# SRAM.net
KiCad netlist of a schematic drawn in Altium Designer
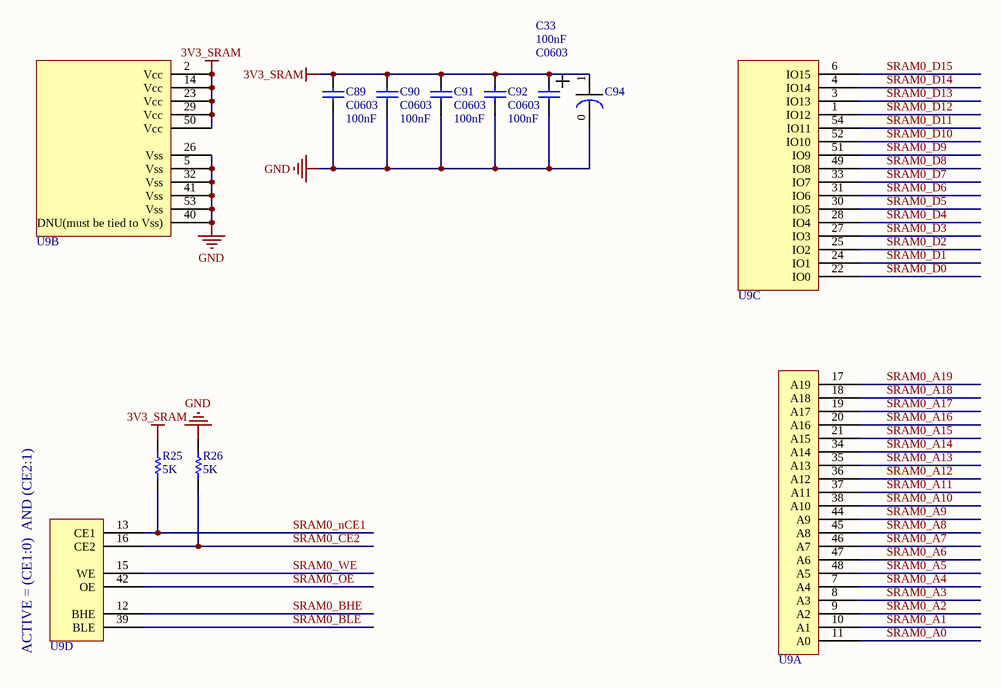
[diagram p0: SRAM.SchDoc]

(export (version "E")
  (design (tool "Eeschema 10.0.6"))
  (components
    (comp (ref "C33")
      (value "C0603")
      (footprint "0603")
      (description "Ceramic Chip Capacitor - Standard")
      (fields (field (name "ALTIUM_VALUE") "100nF") (field (name "PUBLISHER") "Altium Limited"))
      (libsource (lib "KEMET Chip Capacitor") (part "C0603"))
    )
    (comp (ref "C89")
      (value "C0603")
      (footprint "0603")
      (description "Ceramic Chip Capacitor - Standard")
      (fields (field (name "ALTIUM_VALUE") "100nF") (field (name "PUBLISHER") "Altium Limited"))
      (libsource (lib "KEMET Chip Capacitor") (part "C0603"))
    )
    (comp (ref "C90")
      (value "C0603")
      (footprint "0603")
      (description "Ceramic Chip Capacitor - Standard")
      (fields (field (name "ALTIUM_VALUE") "100nF") (field (name "PUBLISHER") "Altium Limited"))
      (libsource (lib "KEMET Chip Capacitor") (part "C0603"))
    )
    (comp (ref "C91")
      (value "C0603")
      (footprint "0603")
      (description "Ceramic Chip Capacitor - Standard")
      (fields (field (name "ALTIUM_VALUE") "100nF") (field (name "PUBLISHER") "Altium Limited"))
      (libsource (lib "KEMET Chip Capacitor") (part "C0603"))
    )
    (comp (ref "C92")
      (value "C0603")
      (footprint "0603")
      (description "Ceramic Chip Capacitor - Standard")
      (fields (field (name "ALTIUM_VALUE") "100nF") (field (name "PUBLISHER") "Altium Limited"))
      (libsource (lib "KEMET Chip Capacitor") (part "C0603"))
    )
    (comp (ref "C94")
      (value "Electrolytic SMD Cap")
      (footprint "22_47u_10A")
      (libsource (lib "SMD_ELECTRLT_CAP") (part "Electrolytic SMD Cap"))
    )
    (comp (ref "R25")
      (value "5K")
      (footprint "ERA-0805")
      (fields (field (name "PUBLISHER") "Altium Limited"))
      (libsource (lib "Panasonic Resistor") (part "ERA6Y"))
    )
    (comp (ref "R26")
      (value "5K")
      (footprint "ERA-0805")
      (fields (field (name "PUBLISHER") "Altium Limited"))
      (libsource (lib "Panasonic Resistor") (part "ERA6Y"))
    )
    (comp (ref "U9")
      (value "SRAM")
      (footprint "PCBComponent_1")
      (description "Static RAM")
      (libsource (lib "cy7c1061av33") (part "CY7C1061AV33"))
    )
  )
  (nets
    (net (code "1") (name "/SRAM0_A0") (class "Default")
      (node (ref "U9") (pin "11") (pinfunction "A0_11") (pintype "passive"))
    )
    (net (code "2") (name "/SRAM0_A1") (class "Default")
      (node (ref "U9") (pin "10") (pinfunction "A1_10") (pintype "passive"))
    )
    (net (code "3") (name "/SRAM0_A2") (class "Default")
      (node (ref "U9") (pin "9") (pinfunction "A2_9") (pintype "passive"))
    )
    (net (code "4") (name "/SRAM0_A3") (class "Default")
      (node (ref "U9") (pin "8") (pinfunction "A3_8") (pintype "passive"))
    )
    (net (code "5") (name "/SRAM0_A4") (class "Default")
      (node (ref "U9") (pin "7") (pinfunction "A4_7") (pintype "passive"))
    )
    (net (code "6") (name "/SRAM0_A5") (class "Default")
      (node (ref "U9") (pin "48") (pinfunction "A5_48") (pintype "passive"))
    )
    (net (code "7") (name "/SRAM0_A6") (class "Default")
      (node (ref "U9") (pin "47") (pinfunction "A6_47") (pintype "passive"))
    )
    (net (code "8") (name "/SRAM0_A7") (class "Default")
      (node (ref "U9") (pin "46") (pinfunction "A7_46") (pintype "passive"))
    )
    (net (code "9") (name "/SRAM0_A8") (class "Default")
      (node (ref "U9") (pin "45") (pinfunction "A8_45") (pintype "passive"))
    )
    (net (code "10") (name "/SRAM0_A9") (class "Default")
      (node (ref "U9") (pin "44") (pinfunction "A9_44") (pintype "passive"))
    )
    (net (code "11") (name "/SRAM0_A10") (class "Default")
      (node (ref "U9") (pin "38") (pinfunction "A10_38") (pintype "passive"))
    )
    (net (code "12") (name "/SRAM0_A11") (class "Default")
      (node (ref "U9") (pin "37") (pinfunction "A11_37") (pintype "passive"))
    )
    (net (code "13") (name "/SRAM0_A12") (class "Default")
      (node (ref "U9") (pin "36") (pinfunction "A12_36") (pintype "passive"))
    )
    (net (code "14") (name "/SRAM0_A13") (class "Default")
      (node (ref "U9") (pin "35") (pinfunction "A13_35") (pintype "passive"))
    )
    (net (code "15") (name "/SRAM0_A14") (class "Default")
      (node (ref "U9") (pin "34") (pinfunction "A14_34") (pintype "passive"))
    )
    (net (code "16") (name "/SRAM0_A15") (class "Default")
      (node (ref "U9") (pin "21") (pinfunction "A15_21") (pintype "passive"))
    )
    (net (code "17") (name "/SRAM0_A16") (class "Default")
      (node (ref "U9") (pin "20") (pinfunction "A16_20") (pintype "passive"))
    )
    (net (code "18") (name "/SRAM0_A17") (class "Default")
      (node (ref "U9") (pin "19") (pinfunction "A17_19") (pintype "passive"))
    )
    (net (code "19") (name "/SRAM0_A18") (class "Default")
      (node (ref "U9") (pin "18") (pinfunction "A18_18") (pintype "passive"))
    )
    (net (code "20") (name "/SRAM0_A19") (class "Default")
      (node (ref "U9") (pin "17") (pinfunction "A19_17") (pintype "passive"))
    )
    (net (code "21") (name "/SRAM0_BHE") (class "Default")
      (node (ref "U9") (pin "12") (pinfunction "BHE_12") (pintype "passive"))
    )
    (net (code "22") (name "/SRAM0_BLE") (class "Default")
      (node (ref "U9") (pin "39") (pinfunction "BLE_39") (pintype "passive"))
    )
    (net (code "23") (name "/SRAM0_CE2") (class "Default")
      (node (ref "R26") (pin "1") (pinfunction "1_1") (pintype "passive"))
      (node (ref "U9") (pin "16") (pinfunction "CE2_16") (pintype "passive"))
    )
    (net (code "24") (name "/SRAM0_D0") (class "Default")
      (node (ref "U9") (pin "22") (pinfunction "IO0_22") (pintype "passive"))
    )
    (net (code "25") (name "/SRAM0_D1") (class "Default")
      (node (ref "U9") (pin "24") (pinfunction "IO1_24") (pintype "passive"))
    )
    (net (code "26") (name "/SRAM0_D2") (class "Default")
      (node (ref "U9") (pin "25") (pinfunction "IO2_25") (pintype "passive"))
    )
    (net (code "27") (name "/SRAM0_D3") (class "Default")
      (node (ref "U9") (pin "27") (pinfunction "IO3_27") (pintype "passive"))
    )
    (net (code "28") (name "/SRAM0_D4") (class "Default")
      (node (ref "U9") (pin "28") (pinfunction "IO4_28") (pintype "passive"))
    )
    (net (code "29") (name "/SRAM0_D5") (class "Default")
      (node (ref "U9") (pin "30") (pinfunction "IO5_30") (pintype "passive"))
    )
    (net (code "30") (name "/SRAM0_D6") (class "Default")
      (node (ref "U9") (pin "31") (pinfunction "IO6_31") (pintype "passive"))
    )
    (net (code "31") (name "/SRAM0_D7") (class "Default")
      (node (ref "U9") (pin "33") (pinfunction "IO7_33") (pintype "passive"))
    )
    (net (code "32") (name "/SRAM0_D8") (class "Default")
      (node (ref "U9") (pin "49") (pinfunction "IO8_49") (pintype "passive"))
    )
    (net (code "33") (name "/SRAM0_D9") (class "Default")
      (node (ref "U9") (pin "51") (pinfunction "IO9_51") (pintype "passive"))
    )
    (net (code "34") (name "/SRAM0_D10") (class "Default")
      (node (ref "U9") (pin "52") (pinfunction "IO10_52") (pintype "passive"))
    )
    (net (code "35") (name "/SRAM0_D11") (class "Default")
      (node (ref "U9") (pin "54") (pinfunction "IO11_54") (pintype "passive"))
    )
    (net (code "36") (name "/SRAM0_D12") (class "Default")
      (node (ref "U9") (pin "1") (pinfunction "IO12_1") (pintype "passive"))
    )
    (net (code "37") (name "/SRAM0_D13") (class "Default")
      (node (ref "U9") (pin "3") (pinfunction "IO13_3") (pintype "passive"))
    )
    (net (code "38") (name "/SRAM0_D14") (class "Default")
      (node (ref "U9") (pin "4") (pinfunction "IO14_4") (pintype "passive"))
    )
    (net (code "39") (name "/SRAM0_D15") (class "Default")
      (node (ref "U9") (pin "6") (pinfunction "IO15_6") (pintype "passive"))
    )
    (net (code "40") (name "/SRAM0_OE") (class "Default")
      (node (ref "U9") (pin "42") (pinfunction "OE_42") (pintype "passive"))
    )
    (net (code "41") (name "/SRAM0_WE") (class "Default")
      (node (ref "U9") (pin "15") (pinfunction "WE_15") (pintype "passive"))
    )
    (net (code "42") (name "/SRAM0_nCE1") (class "Default")
      (node (ref "R25") (pin "1") (pinfunction "1_1") (pintype "passive"))
      (node (ref "U9") (pin "13") (pinfunction "CE1_13") (pintype "passive"))
    )
    (net (code "43") (name "3V3_SRAM") (class "Default")
      (node (ref "C33") (pin "2") (pinfunction "2_2") (pintype "passive"))
      (node (ref "C89") (pin "2") (pinfunction "2_2") (pintype "passive"))
      (node (ref "C90") (pin "2") (pinfunction "2_2") (pintype "passive"))
      (node (ref "C91") (pin "2") (pinfunction "2_2") (pintype "passive"))
      (node (ref "C92") (pin "2") (pinfunction "2_2") (pintype "passive"))
      (node (ref "C94") (pin "1") (pinfunction "1_1") (pintype "passive"))
      (node (ref "R25") (pin "2") (pinfunction "2_2") (pintype "passive"))
      (node (ref "U9") (pin "14") (pinfunction "Vcc_14") (pintype "power_in"))
      (node (ref "U9") (pin "2") (pinfunction "Vcc_2") (pintype "power_in"))
      (node (ref "U9") (pin "23") (pinfunction "Vcc_23") (pintype "power_in"))
      (node (ref "U9") (pin "29") (pinfunction "Vcc_29") (pintype "power_in"))
      (node (ref "U9") (pin "50") (pinfunction "Vcc_50") (pintype "power_in"))
    )
    (net (code "44") (name "GND") (class "Default")
      (node (ref "C33") (pin "1") (pinfunction "1_1") (pintype "passive"))
      (node (ref "C89") (pin "1") (pinfunction "1_1") (pintype "passive"))
      (node (ref "C90") (pin "1") (pinfunction "1_1") (pintype "passive"))
      (node (ref "C91") (pin "1") (pinfunction "1_1") (pintype "passive"))
      (node (ref "C92") (pin "1") (pinfunction "1_1") (pintype "passive"))
      (node (ref "C94") (pin "0") (pinfunction "0_0") (pintype "passive"))
      (node (ref "R26") (pin "2") (pinfunction "2_2") (pintype "passive"))
      (node (ref "U9") (pin "26") (pinfunction "Vss_26") (pintype "power_in"))
      (node (ref "U9") (pin "32") (pinfunction "Vss_32") (pintype "power_in"))
      (node (ref "U9") (pin "40") (pinfunction "DNU(must_be_tied_to_Vss)_40") (pintype "passive"))
      (node (ref "U9") (pin "41") (pinfunction "Vss_41") (pintype "passive"))
      (node (ref "U9") (pin "5") (pinfunction "Vss_5") (pintype "power_in"))
      (node (ref "U9") (pin "53") (pinfunction "Vss_53") (pintype "power_in"))
    )
  )
)
